# PCB_DYBoard_Bandmaster_V2_SCH1.net
KiCad netlist of a schematic drawn in Altium Designer
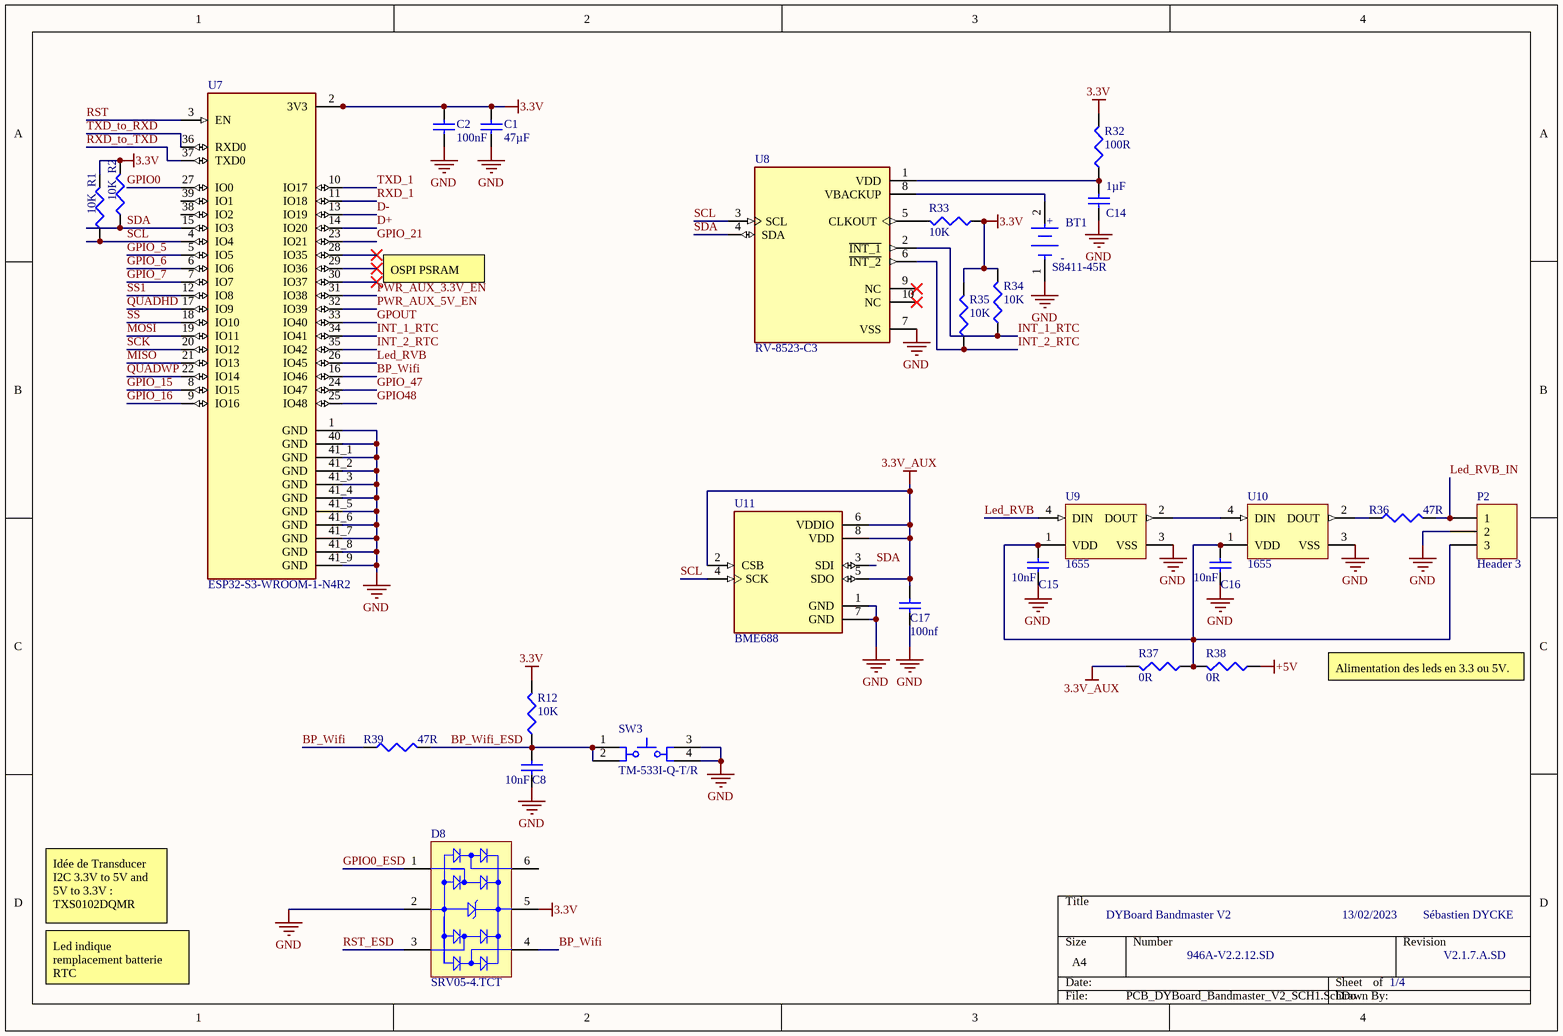
[diagram p0: PCB_DYBoard_Bandmaster_V2_SCH1.SchDoc]

(export (version "E")
  (design (tool "Eeschema 10.0.6"))
  (components
    (comp (ref "BT1")
      (value "S8411-45R")
      (footprint "FP-S8411-45R-MFG")
      (description "BATTERY HOLDER COIN 12MM SMD")
      (libsource (lib "Altium Content Vault") (part "60d3b5b901a8747834971d0eb8cf3fd"))
    )
    (comp (ref "C1")
      (value "47µF")
      (footprint "1608[0603]")
      (description "Capacitor (Semiconductor SIM Model)")
      (fields (field (name "Comment") "Cap Semi") (field (name "PUBLISHER") "Altium Limited"))
      (libsource (lib "Miscellaneous Devices") (part "Cap Semi"))
    )
    (comp (ref "C2")
      (value "100nF")
      (footprint "1608[0603]")
      (description "Capacitor (Semiconductor SIM Model)")
      (fields (field (name "Comment") "Cap Semi") (field (name "PUBLISHER") "Altium Limited"))
      (libsource (lib "Miscellaneous Devices") (part "Cap Semi"))
    )
    (comp (ref "C8")
      (value "10nF")
      (footprint "1608[0603]")
      (description "Capacitor (Semiconductor SIM Model)")
      (fields (field (name "Comment") "Cap Semi") (field (name "PUBLISHER") "Altium Limited"))
      (libsource (lib "Miscellaneous Devices") (part "Cap Semi"))
    )
    (comp (ref "C14")
      (value "1µF")
      (footprint "1608[0603]")
      (description "Capacitor (Semiconductor SIM Model)")
      (fields (field (name "Comment") "Cap Semi") (field (name "PUBLISHER") "Altium Limited"))
      (libsource (lib "Miscellaneous Devices") (part "Cap Semi"))
    )
    (comp (ref "C15")
      (value "10nF")
      (footprint "1608[0603]")
      (description "Capacitor (Semiconductor SIM Model)")
      (fields (field (name "Comment") "Cap Semi") (field (name "PUBLISHER") "Altium Limited"))
      (libsource (lib "Miscellaneous Devices") (part "Cap Semi"))
    )
    (comp (ref "C16")
      (value "10nF")
      (footprint "1608[0603]")
      (description "Capacitor (Semiconductor SIM Model)")
      (fields (field (name "Comment") "Cap Semi") (field (name "PUBLISHER") "Altium Limited"))
      (libsource (lib "Miscellaneous Devices") (part "Cap Semi"))
    )
    (comp (ref "C17")
      (value "100nf")
      (footprint "1608[0603]")
      (description "Capacitor (Semiconductor SIM Model)")
      (fields (field (name "Comment") "Cap Semi") (field (name "PUBLISHER") "Altium Limited"))
      (libsource (lib "Miscellaneous Devices") (part "Cap Semi"))
    )
    (comp (ref "D8")
      (value "SRV05-4.TCT")
      (footprint "SMTC-SOT23-6_V")
      (fields (field (name "MANUFACTURER") "Semtech"))
      (libsource (lib "Altium Content Vault") (part "STM-USB_DVI_HDMIULC6-4SC6X-SOT23-6L"))
    )
    (comp (ref "P2")
      (value "Header 3")
      (footprint "HDR1X3")
      (description "Header, 3-Pin")
      (fields (field (name "PUBLISHER") "Altium Limited"))
      (libsource (lib "Miscellaneous Connectors") (part "Header 3"))
    )
    (comp (ref "R1")
      (value "10K")
      (footprint "J1-0603")
      (description "Resistor")
      (fields (field (name "Comment") "Res3") (field (name "PUBLISHER") "Altium Limited"))
      (libsource (lib "Miscellaneous Devices") (part "Res3"))
    )
    (comp (ref "R2")
      (value "10K")
      (footprint "J1-0603")
      (description "Resistor")
      (fields (field (name "Comment") "Res3") (field (name "PUBLISHER") "Altium Limited"))
      (libsource (lib "Miscellaneous Devices") (part "Res3"))
    )
    (comp (ref "R12")
      (value "10K")
      (footprint "J1-0603")
      (description "Resistor")
      (fields (field (name "Comment") "Res3") (field (name "PUBLISHER") "Altium Limited"))
      (libsource (lib "Miscellaneous Devices") (part "Res3"))
    )
    (comp (ref "R32")
      (value "100R")
      (footprint "J1-0603")
      (description "Resistor")
      (fields (field (name "Comment") "Res3") (field (name "PUBLISHER") "Altium Limited"))
      (libsource (lib "Miscellaneous Devices") (part "Res3"))
    )
    (comp (ref "R33")
      (value "10K")
      (footprint "J1-0603")
      (description "Resistor")
      (fields (field (name "Comment") "Res3") (field (name "PUBLISHER") "Altium Limited"))
      (libsource (lib "Miscellaneous Devices") (part "Res3"))
    )
    (comp (ref "R34")
      (value "10K")
      (footprint "J1-0603")
      (description "Resistor")
      (fields (field (name "Comment") "Res3") (field (name "PUBLISHER") "Altium Limited"))
      (libsource (lib "Miscellaneous Devices") (part "Res3"))
    )
    (comp (ref "R35")
      (value "10K")
      (footprint "J1-0603")
      (description "Resistor")
      (fields (field (name "Comment") "Res3") (field (name "PUBLISHER") "Altium Limited"))
      (libsource (lib "Miscellaneous Devices") (part "Res3"))
    )
    (comp (ref "R36")
      (value "47R")
      (footprint "J1-0603")
      (description "Resistor")
      (fields (field (name "Comment") "Res3") (field (name "PUBLISHER") "Altium Limited"))
      (libsource (lib "Miscellaneous Devices") (part "Res3"))
    )
    (comp (ref "R37")
      (value "0R")
      (footprint "J1-0603")
      (description "Resistor")
      (fields (field (name "Comment") "Res3") (field (name "PUBLISHER") "Altium Limited"))
      (libsource (lib "Miscellaneous Devices") (part "Res3"))
    )
    (comp (ref "R38")
      (value "0R")
      (footprint "J1-0603")
      (description "Resistor")
      (fields (field (name "Comment") "Res3") (field (name "PUBLISHER") "Altium Limited"))
      (libsource (lib "Miscellaneous Devices") (part "Res3"))
    )
    (comp (ref "R39")
      (value "47R")
      (footprint "J1-0603")
      (description "Resistor")
      (fields (field (name "Comment") "Res3") (field (name "PUBLISHER") "Altium Limited"))
      (libsource (lib "Miscellaneous Devices") (part "Res3"))
    )
    (comp (ref "SW3")
      (value "TM-533I-Q-T/R")
      (footprint "MULT-TM-533I-Q_V")
      (description "TACT Switch, SPNO, -25 to 70 degC, 4-Pin SMD, RoHS, Tape and Reel")
      (libsource (lib "Altium Content Vault") (part "SW-SPST-NO-4"))
    )
    (comp (ref "U7")
      (value "ESP32-S3-WROOM-1-N4R2")
      (footprint "XCVR_ESP32-S3-WROOM-1-N4R2")
      (description "Bluetooth, WiFi 802.11b/g/n, Bluetooth v5.0 Transceiver Module 2.4GHz PCB Trace Surface Mount")
      (fields (field (name "MF") "Espressif Systems"))
      (libsource (lib "ESP32-S3-WROOM-1-N4R2") (part "ESP32-S3-WROOM-1-N4R2"))
    )
    (comp (ref "U8")
      (value "RV-8523-C3")
      (footprint "IC_RV-8523-C3")
      (libsource (lib "RV-8523-C3") (part "RV-8523-C3"))
    )
    (comp (ref "U9")
      (value "1655")
      (footprint "ADA-RGB-1655_V")
      (fields (field (name "MANUFACTURER") "Adafruit-Industries-LLC"))
      (libsource (lib "Altium Content Vault") (part "ADA-RGB-1655-4"))
    )
    (comp (ref "U10")
      (value "1655")
      (footprint "ADA-RGB-1655_V")
      (fields (field (name "MANUFACTURER") "Adafruit-Industries-LLC"))
      (libsource (lib "Altium Content Vault") (part "ADA-RGB-1655-4"))
    )
    (comp (ref "U11")
      (value "BME688")
      (footprint "IC_BME688")
      (description "Gas sensor measuring relative humidity, barometric pressure, ambient temperature and gas (VOC)")
      (libsource (lib "BME688") (part "BME688"))
    )
  )
  (nets
    (net (code "1") (name "+5V") (class "Default")
      (node (ref "R38") (pin "1") (pinfunction "1_1") (pintype "passive"))
    )
    (net (code "3") (name "/BP_Wifi") (class "Default")
      (node (ref "D8") (pin "4") (pinfunction "I/O_3_4") (pintype "passive"))
      (node (ref "R39") (pin "1") (pinfunction "1_1") (pintype "passive"))
      (node (ref "U7") (pin "16") (pinfunction "IO46_16") (pintype "bidirectional"))
    )
    (net (code "4") (name "/BP_Wifi_ESD") (class "Default")
      (node (ref "C8") (pin "2") (pinfunction "2_2") (pintype "passive"))
      (node (ref "R12") (pin "1") (pinfunction "1_1") (pintype "passive"))
      (node (ref "R39") (pin "2") (pinfunction "2_2") (pintype "passive"))
      (node (ref "SW3") (pin "1") (pinfunction "1_1") (pintype "passive"))
      (node (ref "SW3") (pin "2") (pinfunction "2_2") (pintype "passive"))
    )
    (net (code "5") (name "/D+") (class "Default")
      (node (ref "U7") (pin "14") (pinfunction "IO20_14") (pintype "bidirectional"))
    )
    (net (code "6") (name "/D-") (class "Default")
      (node (ref "U7") (pin "13") (pinfunction "IO19_13") (pintype "bidirectional"))
    )
    (net (code "7") (name "/GPIO0") (class "Default")
      (node (ref "U7") (pin "27") (pinfunction "IO0_27") (pintype "bidirectional"))
    )
    (net (code "8") (name "/GPIO0_ESD") (class "Default")
      (node (ref "D8") (pin "1") (pinfunction "I/O_1_1") (pintype "passive"))
    )
    (net (code "9") (name "/GPIO48") (class "Default")
      (node (ref "U7") (pin "25") (pinfunction "IO48_25") (pintype "bidirectional"))
    )
    (net (code "10") (name "/GPIO_5") (class "Default")
      (node (ref "U7") (pin "5") (pinfunction "IO5_5") (pintype "bidirectional"))
    )
    (net (code "11") (name "/GPIO_6") (class "Default")
      (node (ref "U7") (pin "6") (pinfunction "IO6_6") (pintype "bidirectional"))
    )
    (net (code "12") (name "/GPIO_7") (class "Default")
      (node (ref "U7") (pin "7") (pinfunction "IO7_7") (pintype "bidirectional"))
    )
    (net (code "13") (name "/GPIO_15") (class "Default")
      (node (ref "U7") (pin "8") (pinfunction "IO15_8") (pintype "bidirectional"))
    )
    (net (code "14") (name "/GPIO_16") (class "Default")
      (node (ref "U7") (pin "9") (pinfunction "IO16_9") (pintype "bidirectional"))
    )
    (net (code "15") (name "/GPIO_21") (class "Default")
      (node (ref "U7") (pin "23") (pinfunction "IO21_23") (pintype "bidirectional"))
    )
    (net (code "16") (name "/GPIO_47") (class "Default")
      (node (ref "U7") (pin "24") (pinfunction "IO47_24") (pintype "bidirectional"))
    )
    (net (code "17") (name "/GPOUT") (class "Default")
      (node (ref "U7") (pin "33") (pinfunction "IO40_33") (pintype "bidirectional"))
    )
    (net (code "18") (name "/INT_1_RTC") (class "Default")
      (node (ref "R34") (pin "1") (pinfunction "1_1") (pintype "passive"))
      (node (ref "U7") (pin "34") (pinfunction "IO41_34") (pintype "bidirectional"))
      (node (ref "U8") (pin "2") (pinfunction "~{INT_1}_2") (pintype "output"))
    )
    (net (code "19") (name "/INT_2_RTC") (class "Default")
      (node (ref "R35") (pin "1") (pinfunction "1_1") (pintype "passive"))
      (node (ref "U7") (pin "35") (pinfunction "IO42_35") (pintype "bidirectional"))
      (node (ref "U8") (pin "6") (pinfunction "~{INT_2}_6") (pintype "output"))
    )
    (net (code "20") (name "/Led_RVB") (class "Default")
      (node (ref "U7") (pin "26") (pinfunction "IO45_26") (pintype "bidirectional"))
      (node (ref "U9") (pin "4") (pinfunction "DIN_4") (pintype "input"))
    )
    (net (code "21") (name "/Led_RVB_IN") (class "Default")
      (node (ref "P2") (pin "1") (pinfunction "1_1") (pintype "passive"))
      (node (ref "R36") (pin "2") (pinfunction "2_2") (pintype "passive"))
    )
    (net (code "22") (name "/MISO") (class "Default")
      (node (ref "U7") (pin "21") (pinfunction "IO13_21") (pintype "bidirectional"))
    )
    (net (code "23") (name "/MOSI") (class "Default")
      (node (ref "U7") (pin "19") (pinfunction "IO11_19") (pintype "bidirectional"))
    )
    (net (code "24") (name "/PWR_AUX_3.3V_EN") (class "Default")
      (node (ref "U7") (pin "31") (pinfunction "IO38_31") (pintype "bidirectional"))
    )
    (net (code "25") (name "/PWR_AUX_5V_EN") (class "Default")
      (node (ref "U7") (pin "32") (pinfunction "IO39_32") (pintype "bidirectional"))
    )
    (net (code "26") (name "/QUADHD") (class "Default")
      (node (ref "U7") (pin "17") (pinfunction "IO9_17") (pintype "bidirectional"))
    )
    (net (code "27") (name "/QUADWP") (class "Default")
      (node (ref "U7") (pin "22") (pinfunction "IO14_22") (pintype "bidirectional"))
    )
    (net (code "28") (name "/RST") (class "Default")
      (node (ref "U7") (pin "3") (pinfunction "EN_3") (pintype "input"))
    )
    (net (code "29") (name "/RST_ESD") (class "Default")
      (node (ref "D8") (pin "3") (pinfunction "I/O_2_3") (pintype "passive"))
    )
    (net (code "30") (name "/RXD_1") (class "Default")
      (node (ref "U7") (pin "11") (pinfunction "IO18_11") (pintype "bidirectional"))
    )
    (net (code "31") (name "/RXD_to_TXD") (class "Default")
      (node (ref "U7") (pin "37") (pinfunction "TXD0_37") (pintype "bidirectional"))
    )
    (net (code "32") (name "/SCK") (class "Default")
      (node (ref "U7") (pin "20") (pinfunction "IO12_20") (pintype "bidirectional"))
    )
    (net (code "33") (name "/SCL") (class "Default")
      (node (ref "R1") (pin "1") (pinfunction "1_1") (pintype "passive"))
      (node (ref "U11") (pin "4") (pinfunction "SCK_4") (pintype "input"))
      (node (ref "U7") (pin "4") (pinfunction "IO4_4") (pintype "bidirectional"))
      (node (ref "U8") (pin "3") (pinfunction "SCL_3") (pintype "input"))
    )
    (net (code "34") (name "/SDA") (class "Default")
      (node (ref "R2") (pin "1") (pinfunction "1_1") (pintype "passive"))
      (node (ref "U11") (pin "3") (pinfunction "SDI_3") (pintype "bidirectional"))
      (node (ref "U7") (pin "15") (pinfunction "IO3_15") (pintype "bidirectional"))
      (node (ref "U8") (pin "4") (pinfunction "SDA_4") (pintype "bidirectional"))
    )
    (net (code "35") (name "/SS") (class "Default")
      (node (ref "U7") (pin "18") (pinfunction "IO10_18") (pintype "bidirectional"))
    )
    (net (code "36") (name "/SS1") (class "Default")
      (node (ref "U7") (pin "12") (pinfunction "IO8_12") (pintype "bidirectional"))
    )
    (net (code "37") (name "/TXD_1") (class "Default")
      (node (ref "U7") (pin "10") (pinfunction "IO17_10") (pintype "bidirectional"))
    )
    (net (code "38") (name "/TXD_to_RXD") (class "Default")
      (node (ref "U7") (pin "36") (pinfunction "RXD0_36") (pintype "bidirectional"))
    )
    (net (code "39") (name "3.3V") (class "Default")
      (node (ref "C1") (pin "2") (pinfunction "2_2") (pintype "passive"))
      (node (ref "C2") (pin "2") (pinfunction "2_2") (pintype "passive"))
      (node (ref "D8") (pin "5") (pinfunction "VBUS_5") (pintype "passive"))
      (node (ref "R1") (pin "2") (pinfunction "2_2") (pintype "passive"))
      (node (ref "R12") (pin "2") (pinfunction "2_2") (pintype "passive"))
      (node (ref "R2") (pin "2") (pinfunction "2_2") (pintype "passive"))
      (node (ref "R32") (pin "2") (pinfunction "2_2") (pintype "passive"))
      (node (ref "R33") (pin "1") (pinfunction "1_1") (pintype "passive"))
      (node (ref "R34") (pin "2") (pinfunction "2_2") (pintype "passive"))
      (node (ref "R35") (pin "2") (pinfunction "2_2") (pintype "passive"))
      (node (ref "U7") (pin "2") (pinfunction "3V3_2") (pintype "power_in"))
    )
    (net (code "40") (name "3.3V_AUX") (class "Default")
      (node (ref "C17") (pin "2") (pinfunction "2_2") (pintype "passive"))
      (node (ref "R37") (pin "2") (pinfunction "2_2") (pintype "passive"))
      (node (ref "U11") (pin "2") (pinfunction "CSB_2") (pintype "input"))
      (node (ref "U11") (pin "5") (pinfunction "SDO_5") (pintype "bidirectional"))
      (node (ref "U11") (pin "6") (pinfunction "VDDIO_6") (pintype "power_in"))
      (node (ref "U11") (pin "8") (pinfunction "VDD_8") (pintype "power_in"))
    )
    (net (code "41") (name "GND") (class "Default")
      (node (ref "BT1") (pin "1") (pinfunction "C_1") (pintype "passive"))
      (node (ref "C1") (pin "1") (pinfunction "1_1") (pintype "passive"))
      (node (ref "C14") (pin "1") (pinfunction "1_1") (pintype "passive"))
      (node (ref "C15") (pin "1") (pinfunction "1_1") (pintype "passive"))
      (node (ref "C16") (pin "1") (pinfunction "1_1") (pintype "passive"))
      (node (ref "C17") (pin "1") (pinfunction "1_1") (pintype "passive"))
      (node (ref "C2") (pin "1") (pinfunction "1_1") (pintype "passive"))
      (node (ref "C8") (pin "1") (pinfunction "1_1") (pintype "passive"))
      (node (ref "D8") (pin "2") (pinfunction "GND_2") (pintype "passive"))
      (node (ref "P2") (pin "2") (pinfunction "2_2") (pintype "passive"))
      (node (ref "SW3") (pin "3") (pinfunction "3_3") (pintype "passive"))
      (node (ref "SW3") (pin "4") (pinfunction "4_4") (pintype "passive"))
      (node (ref "U10") (pin "3") (pinfunction "VSS_3") (pintype "power_in"))
      (node (ref "U11") (pin "1") (pinfunction "GND_1") (pintype "power_in"))
      (node (ref "U11") (pin "7") (pinfunction "GND_7") (pintype "power_in"))
      (node (ref "U7") (pin "1") (pinfunction "GND_1") (pintype "power_in"))
      (node (ref "U7") (pin "40") (pinfunction "GND_40") (pintype "power_in"))
      (node (ref "U7") (pin "41_1") (pinfunction "GND_41_1") (pintype "power_in"))
      (node (ref "U7") (pin "41_2") (pinfunction "GND_41_2") (pintype "power_in"))
      (node (ref "U7") (pin "41_3") (pinfunction "GND_41_3") (pintype "power_in"))
      (node (ref "U7") (pin "41_4") (pinfunction "GND_41_4") (pintype "power_in"))
      (node (ref "U7") (pin "41_5") (pinfunction "GND_41_5") (pintype "power_in"))
      (node (ref "U7") (pin "41_6") (pinfunction "GND_41_6") (pintype "power_in"))
      (node (ref "U7") (pin "41_7") (pinfunction "GND_41_7") (pintype "power_in"))
      (node (ref "U7") (pin "41_8") (pinfunction "GND_41_8") (pintype "power_in"))
      (node (ref "U7") (pin "41_9") (pinfunction "GND_41_9") (pintype "power_in"))
      (node (ref "U8") (pin "7") (pinfunction "VSS_7") (pintype "power_in"))
      (node (ref "U9") (pin "3") (pinfunction "VSS_3") (pintype "power_in"))
    )
    (net (code "42") (name "Net-(BT1-A)") (class "Default")
      (node (ref "BT1") (pin "2") (pinfunction "A_2") (pintype "passive"))
      (node (ref "U8") (pin "8") (pinfunction "VBACKUP_8") (pintype "power_in"))
    )
    (net (code "43") (name "Net-(U8-CLKOUT)") (class "Default")
      (node (ref "R33") (pin "2") (pinfunction "2_2") (pintype "passive"))
      (node (ref "U8") (pin "5") (pinfunction "CLKOUT_5") (pintype "output"))
    )
    (net (code "44") (name "Net-(U8-VDD)") (class "Default")
      (node (ref "C14") (pin "2") (pinfunction "2_2") (pintype "passive"))
      (node (ref "R32") (pin "1") (pinfunction "1_1") (pintype "passive"))
      (node (ref "U8") (pin "1") (pinfunction "VDD_1") (pintype "power_in"))
    )
    (net (code "45") (name "Net-(U10-DIN)") (class "Default")
      (node (ref "U10") (pin "4") (pinfunction "DIN_4") (pintype "input"))
      (node (ref "U9") (pin "2") (pinfunction "DOUT_2") (pintype "output"))
    )
    (net (code "46") (name "Net-(U10-DOUT)") (class "Default")
      (node (ref "R36") (pin "1") (pinfunction "1_1") (pintype "passive"))
      (node (ref "U10") (pin "2") (pinfunction "DOUT_2") (pintype "output"))
    )
    (net (code "47") (name "Net-(U10-VDD)") (class "Default")
      (node (ref "C15") (pin "2") (pinfunction "2_2") (pintype "passive"))
      (node (ref "C16") (pin "2") (pinfunction "2_2") (pintype "passive"))
      (node (ref "P2") (pin "3") (pinfunction "3_3") (pintype "passive"))
      (node (ref "R37") (pin "1") (pinfunction "1_1") (pintype "passive"))
      (node (ref "R38") (pin "2") (pinfunction "2_2") (pintype "passive"))
      (node (ref "U10") (pin "1") (pinfunction "VDD_1") (pintype "power_in"))
      (node (ref "U9") (pin "1") (pinfunction "VDD_1") (pintype "power_in"))
    )
    (net (code "48") (name "unconnected-(D8-I{slash}O_4-Pad6)") (class "Default")
      (node (ref "D8") (pin "6") (pinfunction "I/O_4_6") (pintype "passive"))
    )
    (net (code "49") (name "unconnected-(U7-IO1-Pad39)") (class "Default")
      (node (ref "U7") (pin "39") (pinfunction "IO1_39") (pintype "bidirectional"))
    )
    (net (code "50") (name "unconnected-(U7-IO2-Pad38)") (class "Default")
      (node (ref "U7") (pin "38") (pinfunction "IO2_38") (pintype "bidirectional"))
    )
    (net (code "51") (name "unconnected-(U7-IO35-Pad28)") (class "Default")
      (node (ref "U7") (pin "28") (pinfunction "IO35_28") (pintype "bidirectional+no_connect"))
    )
    (net (code "52") (name "unconnected-(U7-IO36-Pad29)") (class "Default")
      (node (ref "U7") (pin "29") (pinfunction "IO36_29") (pintype "bidirectional+no_connect"))
    )
    (net (code "53") (name "unconnected-(U7-IO37-Pad30)") (class "Default")
      (node (ref "U7") (pin "30") (pinfunction "IO37_30") (pintype "bidirectional+no_connect"))
    )
    (net (code "54") (name "unconnected-(U8-NC-Pad9)") (class "Default")
      (node (ref "U8") (pin "9") (pinfunction "NC_9") (pintype "passive+no_connect"))
    )
    (net (code "55") (name "unconnected-(U8-NC-Pad10)") (class "Default")
      (node (ref "U8") (pin "10") (pinfunction "NC_10") (pintype "passive+no_connect"))
    )
  )
)
